# SolderStation_LCD_v2.net
KiCad netlist of a schematic drawn in EAGLE
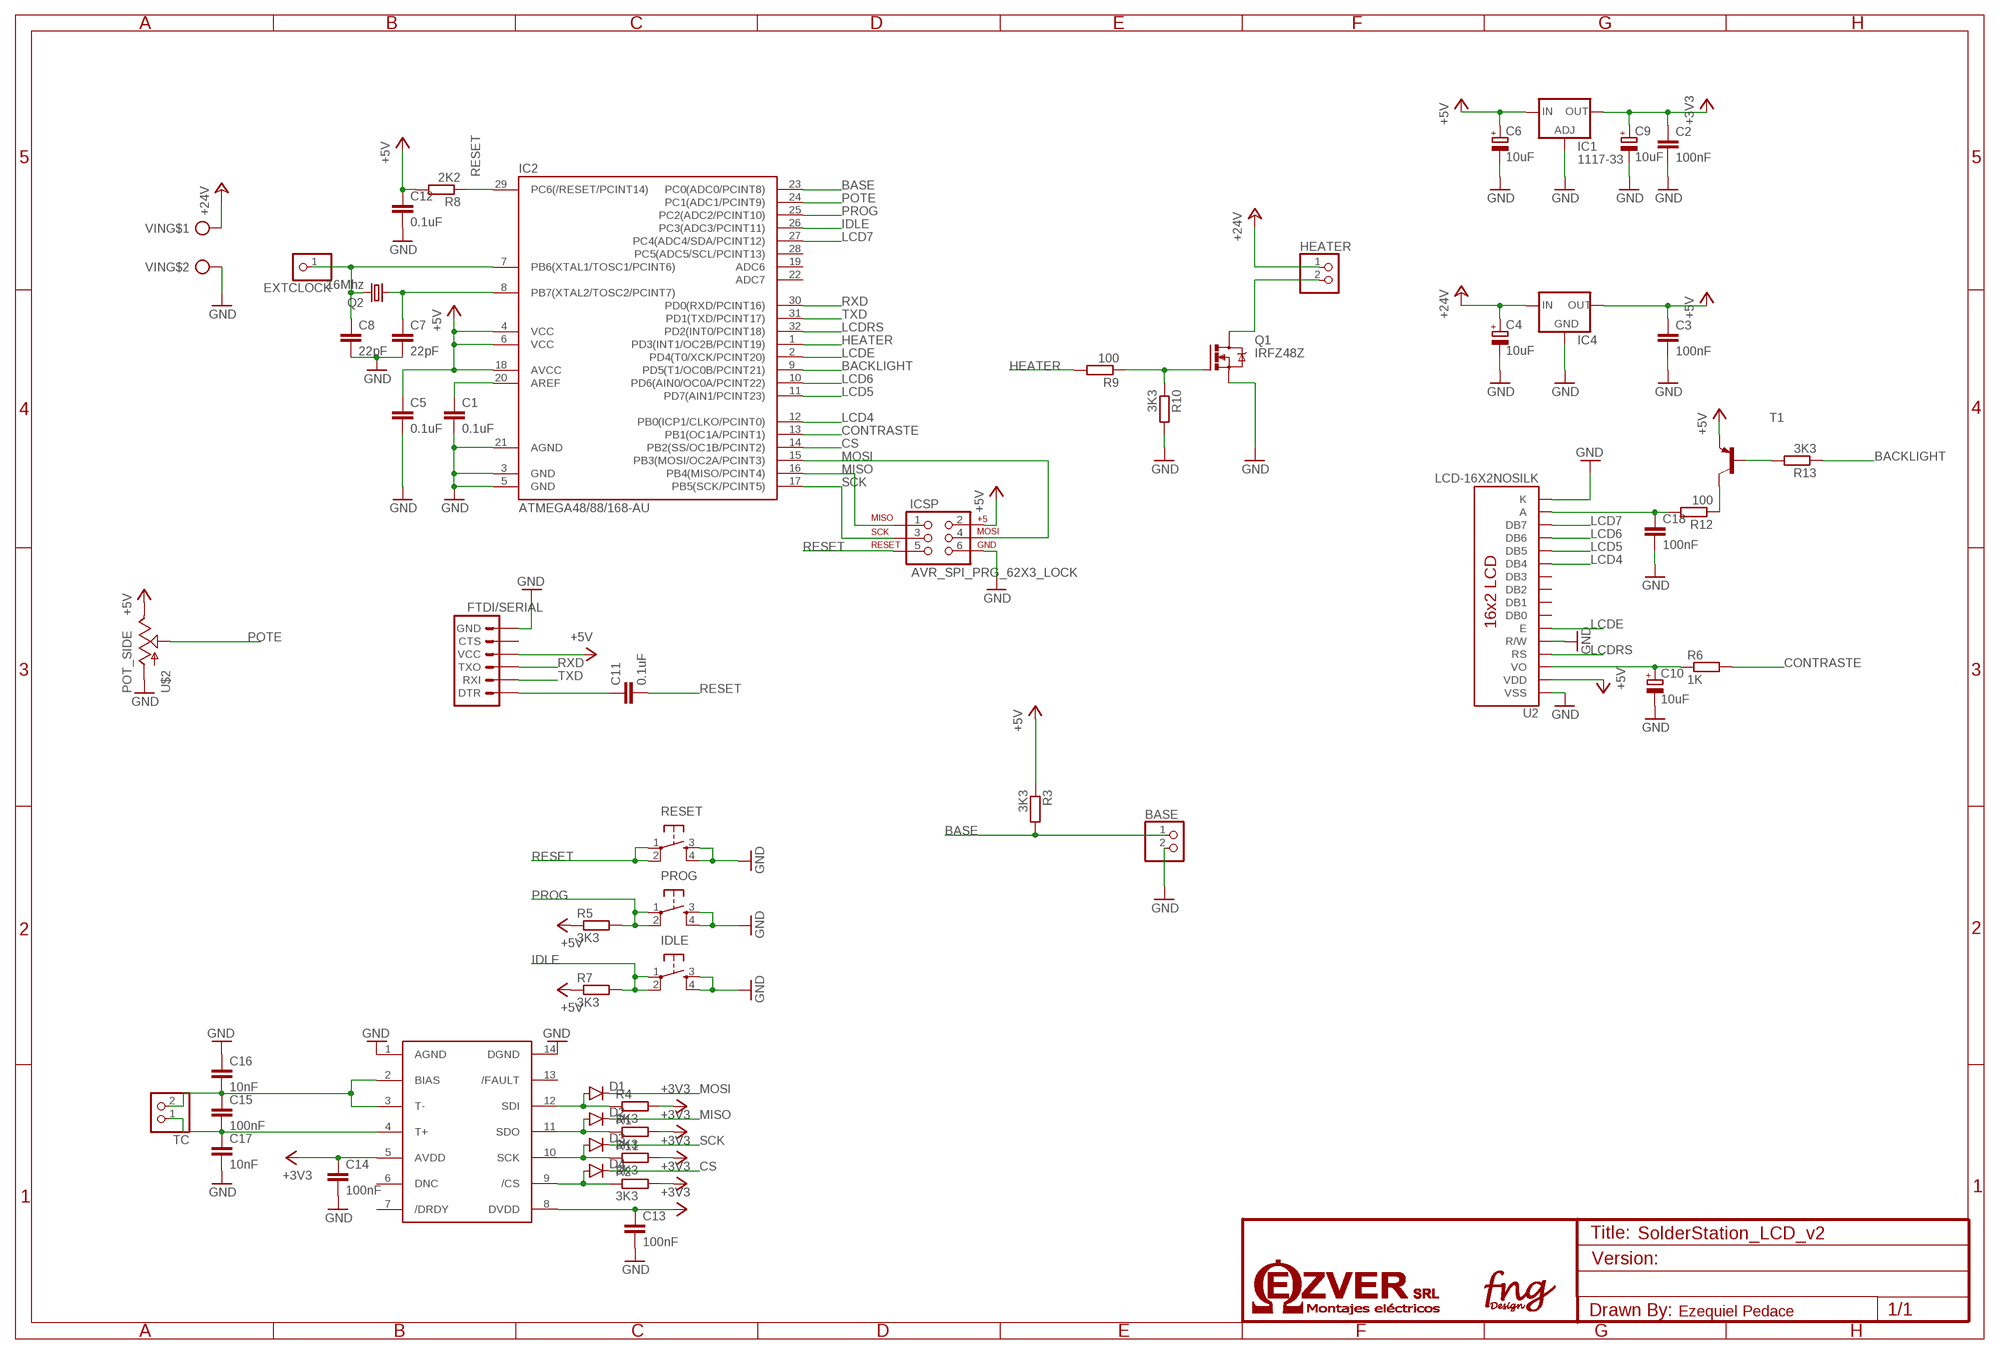
[diagram p0: schematic, sheet 1]

(export (version "E")
  (design (tool "Eeschema 10.0.6"))
  (components
    (comp (ref "BASE")
      (value "PINHD-1X2")
      (footprint "eagle-import:1X02")
      (libsource (lib "eagle-import") (part "PINHD-1X2"))
    )
    (comp (ref "C1")
      (value "0.1uF")
      (footprint "eagle-import:C1206K")
      (libsource (lib "eagle-import") (part "C-EUC1206K"))
    )
    (comp (ref "C2")
      (value "100nF")
      (footprint "eagle-import:C1206K")
      (libsource (lib "eagle-import") (part "C-EUC1206K"))
    )
    (comp (ref "C3")
      (value "100nF")
      (footprint "eagle-import:C1206K")
      (libsource (lib "eagle-import") (part "C-EUC1206K"))
    )
    (comp (ref "C4")
      (value "10uF")
      (footprint "eagle-import:CT3528")
      (libsource (lib "eagle-import") (part "CPOL-EUCT3528"))
    )
    (comp (ref "C5")
      (value "0.1uF")
      (footprint "eagle-import:C1206K")
      (libsource (lib "eagle-import") (part "C-EUC1206K"))
    )
    (comp (ref "C6")
      (value "10uF")
      (footprint "eagle-import:CT3528")
      (libsource (lib "eagle-import") (part "CPOL-EUCT3528"))
    )
    (comp (ref "C7")
      (value "22pF")
      (footprint "eagle-import:C1206K")
      (libsource (lib "eagle-import") (part "C-EUC1206K"))
    )
    (comp (ref "C8")
      (value "22pF")
      (footprint "eagle-import:C1206K")
      (libsource (lib "eagle-import") (part "C-EUC1206K"))
    )
    (comp (ref "C9")
      (value "10uF")
      (footprint "eagle-import:CT3528")
      (libsource (lib "eagle-import") (part "CPOL-EUCT3528"))
    )
    (comp (ref "C10")
      (value "10uF")
      (footprint "eagle-import:CT3528")
      (libsource (lib "eagle-import") (part "CPOL-EUCT3528"))
    )
    (comp (ref "C11")
      (value "0.1uF")
      (footprint "eagle-import:C1206K")
      (libsource (lib "eagle-import") (part "C-EUC1206K"))
    )
    (comp (ref "C12")
      (value "0.1uF")
      (footprint "eagle-import:C1206K")
      (libsource (lib "eagle-import") (part "C-EUC1206K"))
    )
    (comp (ref "C13")
      (value "100nF")
      (footprint "eagle-import:C1206K")
      (libsource (lib "eagle-import") (part "C-EUC1206K"))
    )
    (comp (ref "C14")
      (value "100nF")
      (footprint "eagle-import:C1206K")
      (libsource (lib "eagle-import") (part "C-EUC1206K"))
    )
    (comp (ref "C15")
      (value "100nF")
      (footprint "eagle-import:C1206K")
      (libsource (lib "eagle-import") (part "C-EUC1206K"))
    )
    (comp (ref "C16")
      (value "10nF")
      (footprint "eagle-import:C1206K")
      (libsource (lib "eagle-import") (part "C-EUC1206K"))
    )
    (comp (ref "C17")
      (value "10nF")
      (footprint "eagle-import:C1206K")
      (libsource (lib "eagle-import") (part "C-EUC1206K"))
    )
    (comp (ref "C18")
      (value "100nF")
      (footprint "eagle-import:C1206K")
      (libsource (lib "eagle-import") (part "C-EUC1206K"))
    )
    (comp (ref "D1")
      (value "DIODESMA-ALT")
      (footprint "eagle-import:SMA-DIODE_ALT")
      (libsource (lib "eagle-import") (part "DIODESMA-ALT"))
    )
    (comp (ref "D2")
      (value "DIODESMA-ALT")
      (footprint "eagle-import:SMA-DIODE_ALT")
      (libsource (lib "eagle-import") (part "DIODESMA-ALT"))
    )
    (comp (ref "D3")
      (value "DIODESMA-ALT")
      (footprint "eagle-import:SMA-DIODE_ALT")
      (libsource (lib "eagle-import") (part "DIODESMA-ALT"))
    )
    (comp (ref "D4")
      (value "DIODESMA-ALT")
      (footprint "eagle-import:SMA-DIODE_ALT")
      (libsource (lib "eagle-import") (part "DIODESMA-ALT"))
    )
    (comp (ref "EXTCLOCK")
      (value "PINHD-1X1")
      (footprint "eagle-import:1X01")
      (libsource (lib "eagle-import") (part "PINHD-1X1"))
    )
    (comp (ref "FTDI/SERIAL")
      (value "ARDUINO_SERIAL_PROGRAMLOCK")
      (footprint "eagle-import:1X06_LOCK")
      (libsource (lib "eagle-import") (part "ARDUINO_SERIAL_PROGRAMLOCK"))
    )
    (comp (ref "HEATER")
      (value "PINHD-1X2")
      (footprint "eagle-import:1X02")
      (libsource (lib "eagle-import") (part "PINHD-1X2"))
    )
    (comp (ref "IC1")
      (value "1117-33")
      (footprint "eagle-import:DPACK")
      (libsource (lib "eagle-import") (part "LD117A?DT33TR"))
    )
    (comp (ref "IC2")
      (value "ATMEGA48/88/168-AU")
      (footprint "eagle-import:TQFP32-08")
      (libsource (lib "eagle-import") (part "ATMEGA48/88/168-AU"))
    )
    (comp (ref "IC4")
      (value "78XXL")
      (footprint "eagle-import:78XXL")
      (libsource (lib "eagle-import") (part "78XXL"))
    )
    (comp (ref "ICSP")
      (value "AVR_SPI_PRG_62X3_LOCK")
      (footprint "eagle-import:2X3_LOCK")
      (libsource (lib "eagle-import") (part "AVR_SPI_PRG_62X3_LOCK"))
    )
    (comp (ref "IDLE")
      (value "TAC_SWITCHPTH")
      (footprint "eagle-import:TACTILE-PTH")
      (libsource (lib "eagle-import") (part "TAC_SWITCHPTH"))
    )
    (comp (ref "PROG")
      (value "TAC_SWITCHPTH")
      (footprint "eagle-import:TACTILE-PTH")
      (libsource (lib "eagle-import") (part "TAC_SWITCHPTH"))
    )
    (comp (ref "Q1")
      (value "IRFZ48Z")
      (footprint "eagle-import:TO220BH")
      (libsource (lib "eagle-import") (part "IRFZ48Z"))
    )
    (comp (ref "Q2")
      (value "16Mhz")
      (footprint "eagle-import:HC49U70")
      (libsource (lib "eagle-import") (part "CRYSTALHC49U70"))
    )
    (comp (ref "R1")
      (value "3K3")
      (footprint "eagle-import:M1206")
      (libsource (lib "eagle-import") (part "R-EU_M1206"))
    )
    (comp (ref "R2")
      (value "3K3")
      (footprint "eagle-import:M1206")
      (libsource (lib "eagle-import") (part "R-EU_M1206"))
    )
    (comp (ref "R3")
      (value "3K3")
      (footprint "eagle-import:M1206")
      (libsource (lib "eagle-import") (part "R-EU_M1206"))
    )
    (comp (ref "R4")
      (value "3K3")
      (footprint "eagle-import:M1206")
      (libsource (lib "eagle-import") (part "R-EU_M1206"))
    )
    (comp (ref "R5")
      (value "3K3")
      (footprint "eagle-import:M1206")
      (libsource (lib "eagle-import") (part "R-EU_M1206"))
    )
    (comp (ref "R6")
      (value "1K")
      (footprint "eagle-import:M1206")
      (libsource (lib "eagle-import") (part "R-EU_M1206"))
    )
    (comp (ref "R7")
      (value "3K3")
      (footprint "eagle-import:M1206")
      (libsource (lib "eagle-import") (part "R-EU_M1206"))
    )
    (comp (ref "R8")
      (value "2K2")
      (footprint "eagle-import:M1206")
      (libsource (lib "eagle-import") (part "R-EU_M1206"))
    )
    (comp (ref "R9")
      (value "100")
      (footprint "eagle-import:M1206")
      (libsource (lib "eagle-import") (part "R-EU_M1206"))
    )
    (comp (ref "R10")
      (value "3K3")
      (footprint "eagle-import:M1206")
      (libsource (lib "eagle-import") (part "R-EU_M1206"))
    )
    (comp (ref "R11")
      (value "3K3")
      (footprint "eagle-import:M1206")
      (libsource (lib "eagle-import") (part "R-EU_M1206"))
    )
    (comp (ref "R12")
      (value "100")
      (footprint "eagle-import:M1206")
      (libsource (lib "eagle-import") (part "R-EU_M1206"))
    )
    (comp (ref "R13")
      (value "3K3")
      (footprint "eagle-import:M1206")
      (libsource (lib "eagle-import") (part "R-EU_M1206"))
    )
    (comp (ref "RESET")
      (value "TAC_SWITCHPTH")
      (footprint "eagle-import:TACTILE-PTH")
      (libsource (lib "eagle-import") (part "TAC_SWITCHPTH"))
    )
    (comp (ref "T1")
      (value "BC807-40-PNP-SOT23-BEC")
      (footprint "eagle-import:SOT23-BEC")
      (libsource (lib "eagle-import") (part "-PNP-SOT23-BECBC807-40"))
    )
    (comp (ref "TC")
      (value "PINHD-1X2")
      (footprint "eagle-import:1X02")
      (libsource (lib "eagle-import") (part "PINHD-1X2"))
    )
    (comp (ref "TC1")
      (value "MAX31856")
      (footprint "eagle-import:TSSOP-14")
      (libsource (lib "eagle-import") (part "MAX31856"))
    )
    (comp (ref "U$2")
      (value "POT_SIDE")
      (footprint "eagle-import:POT_ALPHA_SIDE")
      (libsource (lib "eagle-import") (part "POT_SIDE"))
    )
    (comp (ref "U2")
      (value "LCD-16X2NOSILK")
      (footprint "eagle-import:LCD-16X2_NOSILK")
      (libsource (lib "eagle-import") (part "LCD-16X2NOSILK"))
    )
    (comp (ref "VIN")
      (value "CON2")
      (footprint "eagle-import:CON2")
      (libsource (lib "eagle-import") (part "CON2"))
    )
  )
  (nets
    (net (code "1") (name "+3V3") (class "Default")
      (node (ref "C13") (pin "1") (pinfunction "1_1") (pintype "passive"))
      (node (ref "C14") (pin "1") (pinfunction "1_1") (pintype "passive"))
      (node (ref "C2") (pin "1") (pinfunction "1_1") (pintype "passive"))
      (node (ref "C9") (pin "+") (pinfunction "+_+") (pintype "passive"))
      (node (ref "IC1") (pin "4") (pinfunction "OUT_4") (pintype "passive"))
      (node (ref "R1") (pin "2") (pinfunction "2_2") (pintype "passive"))
      (node (ref "R11") (pin "2") (pinfunction "2_2") (pintype "passive"))
      (node (ref "R2") (pin "2") (pinfunction "2_2") (pintype "passive"))
      (node (ref "R4") (pin "2") (pinfunction "2_2") (pintype "passive"))
      (node (ref "TC1") (pin "5") (pinfunction "AVDD_5") (pintype "bidirectional"))
      (node (ref "TC1") (pin "8") (pinfunction "DVDD_8") (pintype "bidirectional"))
    )
    (net (code "2") (name "+5V") (class "Default")
      (node (ref "C12") (pin "1") (pinfunction "1_1") (pintype "passive"))
      (node (ref "C3") (pin "1") (pinfunction "1_1") (pintype "passive"))
      (node (ref "C5") (pin "1") (pinfunction "1_1") (pintype "passive"))
      (node (ref "C6") (pin "+") (pinfunction "+_+") (pintype "passive"))
      (node (ref "FTDI/SERIAL") (pin "4") (pinfunction "VCC_4") (pintype "passive"))
      (node (ref "IC1") (pin "3") (pinfunction "IN_3") (pintype "input"))
      (node (ref "IC2") (pin "18") (pinfunction "AVCC_18") (pintype "passive"))
      (node (ref "IC2") (pin "4") (pinfunction "VCC_4") (pintype "power_in"))
      (node (ref "IC2") (pin "6") (pinfunction "VCC_6") (pintype "power_in"))
      (node (ref "IC4") (pin "OUT") (pinfunction "OUT_OUT") (pintype "passive"))
      (node (ref "ICSP") (pin "2") (pinfunction "2_2") (pintype "passive"))
      (node (ref "R3") (pin "1") (pinfunction "1_1") (pintype "passive"))
      (node (ref "R5") (pin "1") (pinfunction "1_1") (pintype "passive"))
      (node (ref "R7") (pin "1") (pinfunction "1_1") (pintype "passive"))
      (node (ref "R8") (pin "2") (pinfunction "2_2") (pintype "passive"))
      (node (ref "T1") (pin "E") (pinfunction "E_E") (pintype "passive"))
      (node (ref "U$2") (pin "3") (pinfunction "E_3") (pintype "passive"))
      (node (ref "U2") (pin "2") (pinfunction "VDD_2") (pintype "power_in"))
    )
    (net (code "3") (name "+24V") (class "Default")
      (node (ref "C4") (pin "+") (pinfunction "+_+") (pintype "passive"))
      (node (ref "HEATER") (pin "1") (pinfunction "1_1") (pintype "passive"))
      (node (ref "IC4") (pin "IN") (pinfunction "IN_IN") (pintype "input"))
      (node (ref "VIN") (pin "1") (pinfunction "KL_1") (pintype "passive"))
    )
    (net (code "4") (name "/BACKLIGHT") (class "Default")
      (node (ref "IC2") (pin "9") (pinfunction "PD5(T1/OC0B/PCINT21)_9") (pintype "bidirectional"))
      (node (ref "R13") (pin "1") (pinfunction "1_1") (pintype "passive"))
    )
    (net (code "5") (name "/BASE") (class "Default")
      (node (ref "BASE") (pin "1") (pinfunction "1_1") (pintype "passive"))
      (node (ref "IC2") (pin "23") (pinfunction "PC0(ADC0/PCINT8)_23") (pintype "bidirectional"))
      (node (ref "R3") (pin "2") (pinfunction "2_2") (pintype "passive"))
    )
    (net (code "6") (name "/CONTRASTE") (class "Default")
      (node (ref "IC2") (pin "13") (pinfunction "PB1(OC1A/PCINT1)_13") (pintype "bidirectional"))
      (node (ref "R6") (pin "2") (pinfunction "2_2") (pintype "passive"))
    )
    (net (code "7") (name "/CS") (class "Default")
      (node (ref "D4") (pin "C") (pinfunction "C_C") (pintype "passive"))
      (node (ref "IC2") (pin "14") (pinfunction "PB2(SS/OC1B/PCINT2)_14") (pintype "bidirectional"))
    )
    (net (code "8") (name "/HEATER") (class "Default")
      (node (ref "IC2") (pin "1") (pinfunction "PD3(INT1/OC2B/PCINT19)_1") (pintype "bidirectional"))
      (node (ref "R9") (pin "2") (pinfunction "2_2") (pintype "passive"))
    )
    (net (code "9") (name "/IDLE") (class "Default")
      (node (ref "IC2") (pin "26") (pinfunction "PC3(ADC3/PCINT11)_26") (pintype "bidirectional"))
      (node (ref "IDLE") (pin "1") (pinfunction "1_1") (pintype "passive"))
      (node (ref "IDLE") (pin "2") (pinfunction "2_2") (pintype "passive"))
      (node (ref "R7") (pin "2") (pinfunction "2_2") (pintype "passive"))
    )
    (net (code "10") (name "/LCD4") (class "Default")
      (node (ref "IC2") (pin "12") (pinfunction "PB0(ICP1/CLKO/PCINT0)_12") (pintype "bidirectional"))
      (node (ref "U2") (pin "11") (pinfunction "DB4_11") (pintype "bidirectional"))
    )
    (net (code "11") (name "/LCD5") (class "Default")
      (node (ref "IC2") (pin "11") (pinfunction "PD7(AIN1/PCINT23)_11") (pintype "bidirectional"))
      (node (ref "U2") (pin "12") (pinfunction "DB5_12") (pintype "bidirectional"))
    )
    (net (code "12") (name "/LCD6") (class "Default")
      (node (ref "IC2") (pin "10") (pinfunction "PD6(AIN0/OC0A/PCINT22)_10") (pintype "bidirectional"))
      (node (ref "U2") (pin "13") (pinfunction "DB6_13") (pintype "bidirectional"))
    )
    (net (code "13") (name "/LCD7") (class "Default")
      (node (ref "IC2") (pin "27") (pinfunction "PC4(ADC4/SDA/PCINT12)_27") (pintype "bidirectional"))
      (node (ref "U2") (pin "14") (pinfunction "DB7_14") (pintype "bidirectional"))
    )
    (net (code "14") (name "/LCDE") (class "Default")
      (node (ref "IC2") (pin "2") (pinfunction "PD4(T0/XCK/PCINT20)_2") (pintype "bidirectional"))
      (node (ref "U2") (pin "6") (pinfunction "E_6") (pintype "input"))
    )
    (net (code "15") (name "/LCDRS") (class "Default")
      (node (ref "IC2") (pin "32") (pinfunction "PD2(INT0/PCINT18)_32") (pintype "bidirectional"))
      (node (ref "U2") (pin "4") (pinfunction "RS_4") (pintype "input"))
    )
    (net (code "16") (name "/MISO") (class "Default")
      (node (ref "D2") (pin "C") (pinfunction "C_C") (pintype "passive"))
      (node (ref "IC2") (pin "16") (pinfunction "PB4(MISO/PCINT4)_16") (pintype "bidirectional"))
      (node (ref "ICSP") (pin "1") (pinfunction "1_1") (pintype "passive"))
    )
    (net (code "17") (name "/MOSI") (class "Default")
      (node (ref "D1") (pin "C") (pinfunction "C_C") (pintype "passive"))
      (node (ref "IC2") (pin "15") (pinfunction "PB3(MOSI/OC2A/PCINT3)_15") (pintype "bidirectional"))
      (node (ref "ICSP") (pin "4") (pinfunction "4_4") (pintype "passive"))
    )
    (net (code "18") (name "/POTE") (class "Default")
      (node (ref "IC2") (pin "24") (pinfunction "PC1(ADC1/PCINT9)_24") (pintype "bidirectional"))
      (node (ref "U$2") (pin "2") (pinfunction "S_2") (pintype "passive"))
    )
    (net (code "19") (name "/PROG") (class "Default")
      (node (ref "IC2") (pin "25") (pinfunction "PC2(ADC2/PCINT10)_25") (pintype "bidirectional"))
      (node (ref "PROG") (pin "1") (pinfunction "1_1") (pintype "passive"))
      (node (ref "PROG") (pin "2") (pinfunction "2_2") (pintype "passive"))
      (node (ref "R5") (pin "2") (pinfunction "2_2") (pintype "passive"))
    )
    (net (code "20") (name "/RESET") (class "Default")
      (node (ref "C11") (pin "2") (pinfunction "2_2") (pintype "passive"))
      (node (ref "IC2") (pin "29") (pinfunction "PC6(/RESET/PCINT14)_29") (pintype "bidirectional"))
      (node (ref "ICSP") (pin "5") (pinfunction "5_5") (pintype "passive"))
      (node (ref "R8") (pin "1") (pinfunction "1_1") (pintype "passive"))
      (node (ref "RESET") (pin "1") (pinfunction "1_1") (pintype "passive"))
      (node (ref "RESET") (pin "2") (pinfunction "2_2") (pintype "passive"))
    )
    (net (code "21") (name "/RXD") (class "Default")
      (node (ref "FTDI/SERIAL") (pin "3") (pinfunction "TXO_3") (pintype "passive"))
      (node (ref "IC2") (pin "30") (pinfunction "PD0(RXD/PCINT16)_30") (pintype "bidirectional"))
    )
    (net (code "22") (name "/SCK") (class "Default")
      (node (ref "D3") (pin "C") (pinfunction "C_C") (pintype "passive"))
      (node (ref "IC2") (pin "17") (pinfunction "PB5(SCK/PCINT5)_17") (pintype "bidirectional"))
      (node (ref "ICSP") (pin "3") (pinfunction "3_3") (pintype "passive"))
    )
    (net (code "23") (name "/TXD") (class "Default")
      (node (ref "FTDI/SERIAL") (pin "2") (pinfunction "RXI_2") (pintype "passive"))
      (node (ref "IC2") (pin "31") (pinfunction "PD1(TXD/PCINT17)_31") (pintype "bidirectional"))
    )
    (net (code "24") (name "GND") (class "Default")
      (node (ref "BASE") (pin "2") (pinfunction "2_2") (pintype "passive"))
      (node (ref "C1") (pin "2") (pinfunction "2_2") (pintype "passive"))
      (node (ref "C10") (pin "-") (pinfunction "-_-") (pintype "passive"))
      (node (ref "C12") (pin "2") (pinfunction "2_2") (pintype "passive"))
      (node (ref "C13") (pin "2") (pinfunction "2_2") (pintype "passive"))
      (node (ref "C14") (pin "2") (pinfunction "2_2") (pintype "passive"))
      (node (ref "C16") (pin "1") (pinfunction "1_1") (pintype "passive"))
      (node (ref "C17") (pin "2") (pinfunction "2_2") (pintype "passive"))
      (node (ref "C18") (pin "2") (pinfunction "2_2") (pintype "passive"))
      (node (ref "C2") (pin "2") (pinfunction "2_2") (pintype "passive"))
      (node (ref "C3") (pin "2") (pinfunction "2_2") (pintype "passive"))
      (node (ref "C4") (pin "-") (pinfunction "-_-") (pintype "passive"))
      (node (ref "C5") (pin "2") (pinfunction "2_2") (pintype "passive"))
      (node (ref "C6") (pin "-") (pinfunction "-_-") (pintype "passive"))
      (node (ref "C7") (pin "2") (pinfunction "2_2") (pintype "passive"))
      (node (ref "C8") (pin "2") (pinfunction "2_2") (pintype "passive"))
      (node (ref "C9") (pin "-") (pinfunction "-_-") (pintype "passive"))
      (node (ref "FTDI/SERIAL") (pin "6") (pinfunction "GND_6") (pintype "passive"))
      (node (ref "IC1") (pin "1") (pinfunction "ADJ_1") (pintype "input"))
      (node (ref "IC2") (pin "21") (pinfunction "AGND_21") (pintype "power_in"))
      (node (ref "IC2") (pin "3") (pinfunction "GND_3") (pintype "power_in"))
      (node (ref "IC2") (pin "5") (pinfunction "GND_5") (pintype "power_in"))
      (node (ref "IC4") (pin "GND") (pinfunction "GND_GND") (pintype "input"))
      (node (ref "ICSP") (pin "6") (pinfunction "6_6") (pintype "passive"))
      (node (ref "IDLE") (pin "3") (pinfunction "3_3") (pintype "passive"))
      (node (ref "IDLE") (pin "4") (pinfunction "4_4") (pintype "passive"))
      (node (ref "PROG") (pin "3") (pinfunction "3_3") (pintype "passive"))
      (node (ref "PROG") (pin "4") (pinfunction "4_4") (pintype "passive"))
      (node (ref "Q1") (pin "S") (pinfunction "S_S") (pintype "passive"))
      (node (ref "R10") (pin "2") (pinfunction "2_2") (pintype "passive"))
      (node (ref "RESET") (pin "3") (pinfunction "3_3") (pintype "passive"))
      (node (ref "RESET") (pin "4") (pinfunction "4_4") (pintype "passive"))
      (node (ref "TC1") (pin "1") (pinfunction "AGND_1") (pintype "bidirectional"))
      (node (ref "TC1") (pin "14") (pinfunction "DGND_14") (pintype "bidirectional"))
      (node (ref "U$2") (pin "1") (pinfunction "A_1") (pintype "passive"))
      (node (ref "U2") (pin "1") (pinfunction "VSS_1") (pintype "power_in"))
      (node (ref "U2") (pin "16") (pinfunction "K_16") (pintype "power_in"))
      (node (ref "U2") (pin "5") (pinfunction "R/W_5") (pintype "input"))
      (node (ref "VIN") (pin "2") (pinfunction "KL_2") (pintype "passive"))
    )
    (net (code "25") (name "Net-(FTDI/SERIAL-DTR)") (class "Default")
      (node (ref "C11") (pin "1") (pinfunction "1_1") (pintype "passive"))
      (node (ref "FTDI/SERIAL") (pin "1") (pinfunction "DTR_1") (pintype "passive"))
    )
    (net (code "26") (name "Net-(HEATER-Pad2)") (class "Default")
      (node (ref "HEATER") (pin "2") (pinfunction "2_2") (pintype "passive"))
      (node (ref "Q1") (pin "D") (pinfunction "D_D") (pintype "passive"))
    )
    (net (code "27") (name "Net-(IC2-AREF)") (class "Default")
      (node (ref "C1") (pin "1") (pinfunction "1_1") (pintype "passive"))
      (node (ref "IC2") (pin "20") (pinfunction "AREF_20") (pintype "passive"))
    )
    (net (code "28") (name "Net-(IC2-PB6(XTAL1{slash}TOSC1{slash}PCINT6))") (class "Default")
      (node (ref "C8") (pin "1") (pinfunction "1_1") (pintype "passive"))
      (node (ref "EXTCLOCK") (pin "1") (pinfunction "1_1") (pintype "passive"))
      (node (ref "IC2") (pin "7") (pinfunction "PB6(XTAL1/TOSC1/PCINT6)_7") (pintype "bidirectional"))
      (node (ref "Q2") (pin "2") (pinfunction "2_2") (pintype "passive"))
    )
    (net (code "29") (name "Net-(IC2-PB7(XTAL2{slash}TOSC2{slash}PCINT7))") (class "Default")
      (node (ref "C7") (pin "1") (pinfunction "1_1") (pintype "passive"))
      (node (ref "IC2") (pin "8") (pinfunction "PB7(XTAL2/TOSC2/PCINT7)_8") (pintype "bidirectional"))
      (node (ref "Q2") (pin "1") (pinfunction "1_1") (pintype "passive"))
    )
    (net (code "30") (name "Net-(Q1-PadG)") (class "Default")
      (node (ref "Q1") (pin "G") (pinfunction "G_G") (pintype "passive"))
      (node (ref "R10") (pin "1") (pinfunction "1_1") (pintype "passive"))
      (node (ref "R9") (pin "1") (pinfunction "1_1") (pintype "passive"))
    )
    (net (code "31") (name "Net-(R12-Pad1)") (class "Default")
      (node (ref "R12") (pin "1") (pinfunction "1_1") (pintype "passive"))
      (node (ref "T1") (pin "C") (pinfunction "C_C") (pintype "passive"))
    )
    (net (code "32") (name "Net-(R13-Pad2)") (class "Default")
      (node (ref "R13") (pin "2") (pinfunction "2_2") (pintype "passive"))
      (node (ref "T1") (pin "B") (pinfunction "B_B") (pintype "passive"))
    )
    (net (code "33") (name "Net-(TC1-BIAS)") (class "Default")
      (node (ref "C15") (pin "1") (pinfunction "1_1") (pintype "passive"))
      (node (ref "C16") (pin "2") (pinfunction "2_2") (pintype "passive"))
      (node (ref "TC") (pin "2") (pinfunction "2_2") (pintype "passive"))
      (node (ref "TC1") (pin "2") (pinfunction "BIAS_2") (pintype "bidirectional"))
      (node (ref "TC1") (pin "3") (pinfunction "T-_3") (pintype "bidirectional"))
    )
    (net (code "34") (name "Net-(TC1-SCK)") (class "Default")
      (node (ref "D3") (pin "A") (pinfunction "A_A") (pintype "passive"))
      (node (ref "R11") (pin "1") (pinfunction "1_1") (pintype "passive"))
      (node (ref "TC1") (pin "10") (pinfunction "SCK_10") (pintype "bidirectional"))
    )
    (net (code "35") (name "Net-(TC1-SDI)") (class "Default")
      (node (ref "D1") (pin "A") (pinfunction "A_A") (pintype "passive"))
      (node (ref "R4") (pin "1") (pinfunction "1_1") (pintype "passive"))
      (node (ref "TC1") (pin "12") (pinfunction "SDI_12") (pintype "bidirectional"))
    )
    (net (code "36") (name "Net-(TC1-SDO)") (class "Default")
      (node (ref "D2") (pin "A") (pinfunction "A_A") (pintype "passive"))
      (node (ref "R1") (pin "1") (pinfunction "1_1") (pintype "passive"))
      (node (ref "TC1") (pin "11") (pinfunction "SDO_11") (pintype "bidirectional"))
    )
    (net (code "37") (name "Net-(TC1-T+)") (class "Default")
      (node (ref "C15") (pin "2") (pinfunction "2_2") (pintype "passive"))
      (node (ref "C17") (pin "1") (pinfunction "1_1") (pintype "passive"))
      (node (ref "TC") (pin "1") (pinfunction "1_1") (pintype "passive"))
      (node (ref "TC1") (pin "4") (pinfunction "T+_4") (pintype "bidirectional"))
    )
    (net (code "38") (name "Net-(TC1-{slash}CS)") (class "Default")
      (node (ref "D4") (pin "A") (pinfunction "A_A") (pintype "passive"))
      (node (ref "R2") (pin "1") (pinfunction "1_1") (pintype "passive"))
      (node (ref "TC1") (pin "9") (pinfunction "/CS_9") (pintype "bidirectional"))
    )
    (net (code "39") (name "Net-(U2-A)") (class "Default")
      (node (ref "C18") (pin "1") (pinfunction "1_1") (pintype "passive"))
      (node (ref "R12") (pin "2") (pinfunction "2_2") (pintype "passive"))
      (node (ref "U2") (pin "15") (pinfunction "A_15") (pintype "power_in"))
    )
    (net (code "40") (name "Net-(U2-VO)") (class "Default")
      (node (ref "C10") (pin "+") (pinfunction "+_+") (pintype "passive"))
      (node (ref "R6") (pin "1") (pinfunction "1_1") (pintype "passive"))
      (node (ref "U2") (pin "3") (pinfunction "VO_3") (pintype "bidirectional"))
    )
    (net (code "41") (name "unconnected-(FTDI/SERIAL-CTS-Pad5)") (class "Default")
      (node (ref "FTDI/SERIAL") (pin "5") (pinfunction "CTS_5") (pintype "passive"))
    )
    (net (code "42") (name "unconnected-(IC2-ADC6-Pad19)") (class "Default")
      (node (ref "IC2") (pin "19") (pinfunction "ADC6_19") (pintype "passive"))
    )
    (net (code "43") (name "unconnected-(IC2-ADC7-Pad22)") (class "Default")
      (node (ref "IC2") (pin "22") (pinfunction "ADC7_22") (pintype "passive"))
    )
    (net (code "44") (name "unconnected-(IC2-PC5(ADC5{slash}SCL{slash}PCINT13)-Pad28)") (class "Default")
      (node (ref "IC2") (pin "28") (pinfunction "PC5(ADC5/SCL/PCINT13)_28") (pintype "bidirectional"))
    )
    (net (code "45") (name "unconnected-(TC1-DNC-Pad6)") (class "Default")
      (node (ref "TC1") (pin "6") (pinfunction "DNC_6") (pintype "bidirectional"))
    )
    (net (code "46") (name "unconnected-(TC1-{slash}DRDY-Pad7)") (class "Default")
      (node (ref "TC1") (pin "7") (pinfunction "/DRDY_7") (pintype "bidirectional"))
    )
    (net (code "47") (name "unconnected-(TC1-{slash}FAULT-Pad13)") (class "Default")
      (node (ref "TC1") (pin "13") (pinfunction "/FAULT_13") (pintype "bidirectional"))
    )
    (net (code "48") (name "unconnected-(U2-DB0-Pad7)") (class "Default")
      (node (ref "U2") (pin "7") (pinfunction "DB0_7") (pintype "bidirectional"))
    )
    (net (code "49") (name "unconnected-(U2-DB1-Pad8)") (class "Default")
      (node (ref "U2") (pin "8") (pinfunction "DB1_8") (pintype "bidirectional"))
    )
    (net (code "50") (name "unconnected-(U2-DB2-Pad9)") (class "Default")
      (node (ref "U2") (pin "9") (pinfunction "DB2_9") (pintype "bidirectional"))
    )
    (net (code "51") (name "unconnected-(U2-DB3-Pad10)") (class "Default")
      (node (ref "U2") (pin "10") (pinfunction "DB3_10") (pintype "bidirectional"))
    )
  )
)
